# BMS-S02-V00-CellMonitor.net
KiCad netlist of a schematic drawn in Altium Designer
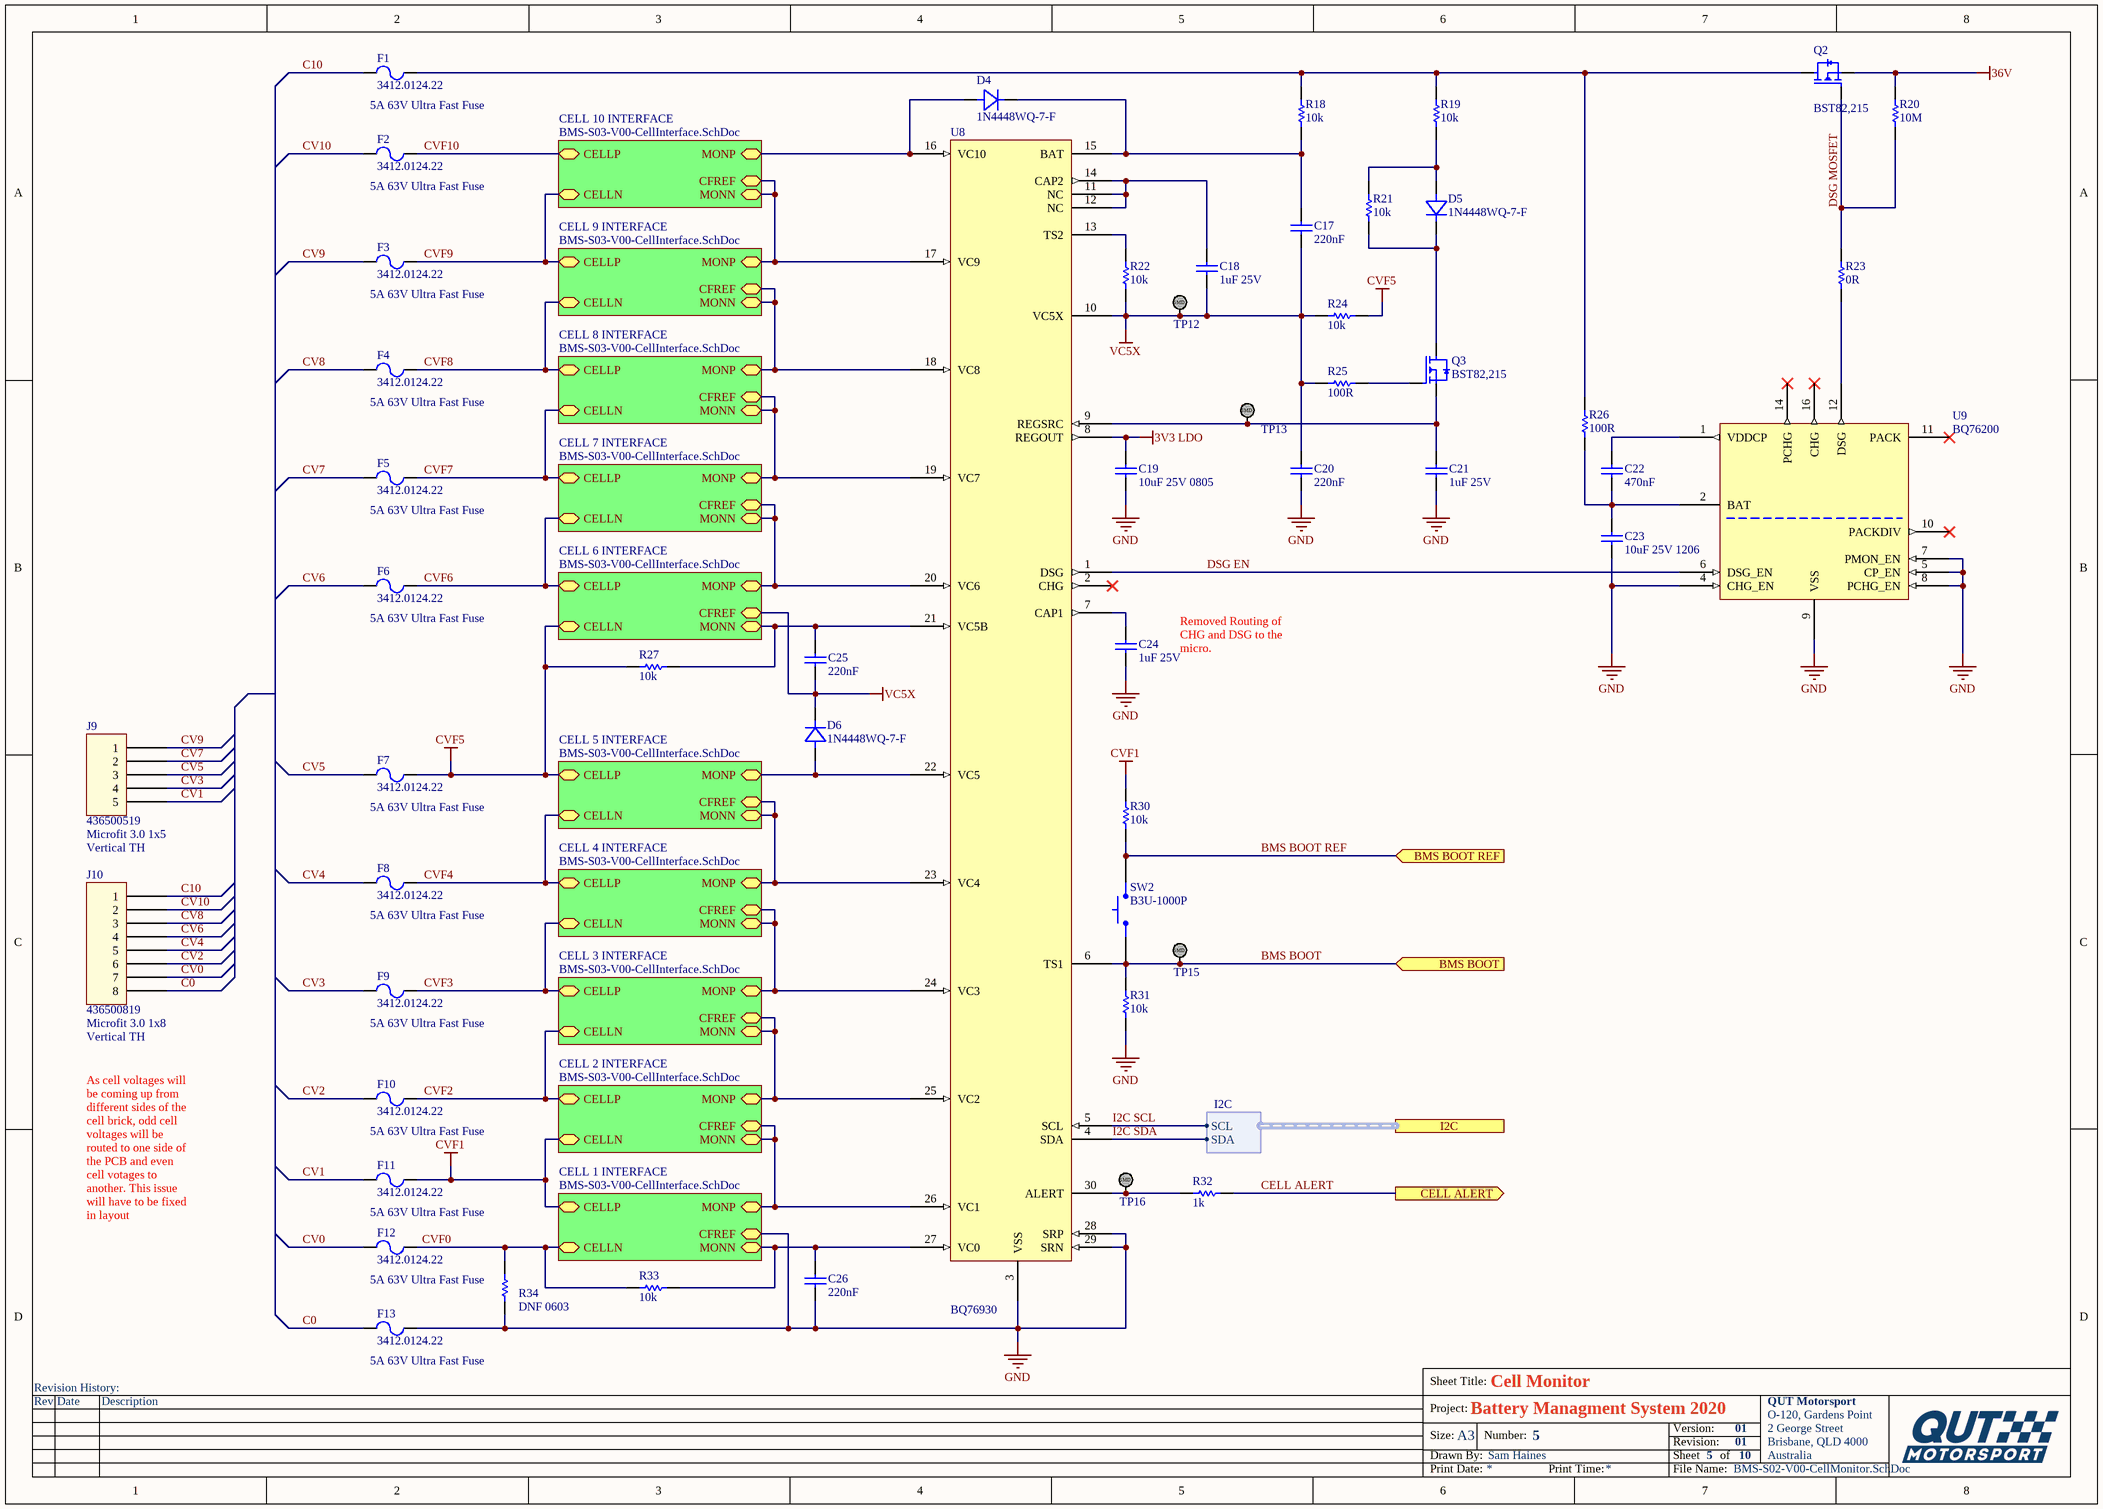
[diagram p0: BMS-S02-V00-CellMonitor.SchDoc]

(export (version "E")
  (design (tool "Eeschema 10.0.6"))
  (components
    (comp (ref "C17")
      (value "220nF")
      (footprint "Cap_Ceramic_0603")
      (description "Capacitor, Ceramic, SMD, 220nF, 50V, 5%, X7R, 0603")
      (libsource (lib "StandardCapacitors") (part "220nF 50V 5% X7R 0603"))
    )
    (comp (ref "C18")
      (value "1uF 25V")
      (footprint "Cap_Ceramic_0603")
      (description "Capacitor, Ceramic, SMD, 1uF, 25V, 5%, X7R, 0603")
      (libsource (lib "StandardCapacitors") (part "1uF 25V 5% X7R 0603"))
    )
    (comp (ref "C19")
      (value "10uF 25V 0805")
      (footprint "Cap_Ceramic_0805")
      (description "Capacitor, Ceramic, SMD, 10uF, 25V, 5%, X7R, 0805")
      (libsource (lib "StandardCapacitors") (part "10uF 25V 5% X7R 0805_1"))
    )
    (comp (ref "C20")
      (value "220nF")
      (footprint "Cap_Ceramic_0603")
      (description "Capacitor, Ceramic, SMD, 220nF, 50V, 5%, X7R, 0603")
      (libsource (lib "StandardCapacitors") (part "220nF 50V 5% X7R 0603"))
    )
    (comp (ref "C21")
      (value "1uF 25V")
      (footprint "Cap_Ceramic_0603")
      (description "Capacitor, Ceramic, SMD, 1uF, 25V, 5%, X7R, 0603")
      (libsource (lib "StandardCapacitors") (part "1uF 25V 5% X7R 0603"))
    )
    (comp (ref "C22")
      (value "470nF")
      (footprint "Cap_Ceramic_0603")
      (description "Capacitor, Ceramic, SMD, 470nF, 50V, 5%, X7R, 0603")
      (libsource (lib "StandardCapacitors") (part "470nF 50V 5% X7R 0603"))
    )
    (comp (ref "C23")
      (value "10uF 25V 1206")
      (footprint "Cap_Ceramic_1206")
      (description "Capacitor, Ceramic, SMD, 10uF, 25V, 10%, X7R, 1206")
      (libsource (lib "StandardCapacitors") (part "10uF 25V 10% X7R 1206"))
    )
    (comp (ref "C24")
      (value "1uF 25V")
      (footprint "Cap_Ceramic_0603")
      (description "Capacitor, Ceramic, SMD, 1uF, 25V, 5%, X7R, 0603")
      (libsource (lib "StandardCapacitors") (part "1uF 25V 5% X7R 0603"))
    )
    (comp (ref "C25")
      (value "220nF")
      (footprint "Cap_Ceramic_0603")
      (description "Capacitor, Ceramic, SMD, 220nF, 50V, 5%, X7R, 0603")
      (libsource (lib "StandardCapacitors") (part "220nF 50V 5% X7R 0603"))
    )
    (comp (ref "C26")
      (value "220nF")
      (footprint "Cap_Ceramic_0603")
      (description "Capacitor, Ceramic, SMD, 220nF, 50V, 5%, X7R, 0603")
      (libsource (lib "StandardCapacitors") (part "220nF 50V 5% X7R 0603"))
    )
    (comp (ref "D4")
      (value "1N4448WQ-7-F")
      (footprint "SMA")
      (description "Diode, SMD, 75V, 5%, 250mA, SOD123")
      (fields
        (field (name "MANUFACTURER") "ON Semiconductor / Fairchild")
        (field (name "MANUFACTURER PART NUMBER") "1N914BWS")
      )
      (libsource (lib "QUTMS_DiodeLibrary") (part "1N4448WQ-7-F"))
    )
    (comp (ref "D5")
      (value "1N4448WQ-7-F")
      (footprint "SMA")
      (description "Diode, SMD, 75V, 5%, 250mA, SOD123")
      (fields
        (field (name "MANUFACTURER") "ON Semiconductor / Fairchild")
        (field (name "MANUFACTURER PART NUMBER") "1N914BWS")
      )
      (libsource (lib "QUTMS_DiodeLibrary") (part "1N4448WQ-7-F"))
    )
    (comp (ref "D6")
      (value "1N4448WQ-7-F")
      (footprint "SMA")
      (description "Diode, SMD, 75V, 5%, 250mA, SOD123")
      (fields
        (field (name "MANUFACTURER") "ON Semiconductor / Fairchild")
        (field (name "MANUFACTURER PART NUMBER") "1N914BWS")
      )
      (libsource (lib "QUTMS_DiodeLibrary") (part "1N4448WQ-7-F"))
    )
    (comp (ref "F1")
      (value "3412.0124.22")
      (footprint "3412.0124.22")
      (description "FUSE BOARD MOUNT 5A 63VDC 0603")
      (libsource (lib "CellMonitor") (part "3412.0124.22"))
    )
    (comp (ref "F2")
      (value "3412.0124.22")
      (footprint "3412.0124.22")
      (description "FUSE BOARD MOUNT 5A 63VDC 0603")
      (libsource (lib "CellMonitor") (part "3412.0124.22"))
    )
    (comp (ref "F3")
      (value "3412.0124.22")
      (footprint "3412.0124.22")
      (description "FUSE BOARD MOUNT 5A 63VDC 0603")
      (libsource (lib "CellMonitor") (part "3412.0124.22"))
    )
    (comp (ref "F4")
      (value "3412.0124.22")
      (footprint "3412.0124.22")
      (description "FUSE BOARD MOUNT 5A 63VDC 0603")
      (libsource (lib "CellMonitor") (part "3412.0124.22"))
    )
    (comp (ref "F5")
      (value "3412.0124.22")
      (footprint "3412.0124.22")
      (description "FUSE BOARD MOUNT 5A 63VDC 0603")
      (libsource (lib "CellMonitor") (part "3412.0124.22"))
    )
    (comp (ref "F6")
      (value "3412.0124.22")
      (footprint "3412.0124.22")
      (description "FUSE BOARD MOUNT 5A 63VDC 0603")
      (libsource (lib "CellMonitor") (part "3412.0124.22"))
    )
    (comp (ref "F7")
      (value "3412.0124.22")
      (footprint "3412.0124.22")
      (description "FUSE BOARD MOUNT 5A 63VDC 0603")
      (libsource (lib "CellMonitor") (part "3412.0124.22"))
    )
    (comp (ref "F8")
      (value "3412.0124.22")
      (footprint "3412.0124.22")
      (description "FUSE BOARD MOUNT 5A 63VDC 0603")
      (libsource (lib "CellMonitor") (part "3412.0124.22"))
    )
    (comp (ref "F9")
      (value "3412.0124.22")
      (footprint "3412.0124.22")
      (description "FUSE BOARD MOUNT 5A 63VDC 0603")
      (libsource (lib "CellMonitor") (part "3412.0124.22"))
    )
    (comp (ref "F10")
      (value "3412.0124.22")
      (footprint "3412.0124.22")
      (description "FUSE BOARD MOUNT 5A 63VDC 0603")
      (libsource (lib "CellMonitor") (part "3412.0124.22"))
    )
    (comp (ref "F11")
      (value "3412.0124.22")
      (footprint "3412.0124.22")
      (description "FUSE BOARD MOUNT 5A 63VDC 0603")
      (libsource (lib "CellMonitor") (part "3412.0124.22"))
    )
    (comp (ref "F12")
      (value "3412.0124.22")
      (footprint "3412.0124.22")
      (description "FUSE BOARD MOUNT 5A 63VDC 0603")
      (libsource (lib "CellMonitor") (part "3412.0124.22"))
    )
    (comp (ref "F13")
      (value "3412.0124.22")
      (footprint "3412.0124.22")
      (description "FUSE BOARD MOUNT 5A 63VDC 0603")
      (libsource (lib "CellMonitor") (part "3412.0124.22"))
    )
    (comp (ref "J9")
      (value "436500519")
      (footprint "Microfit_1X5_V_TH")
      (libsource (lib "QUTMS_MicrofitLibrary") (part "Microfit_1x5"))
    )
    (comp (ref "J10")
      (value "436500819")
      (footprint "Microfit_1X8_V_TH")
      (libsource (lib "QUTMS_MicrofitLibrary") (part "Microfit_1x8"))
    )
    (comp (ref "Q2")
      (value "BST82,215")
      (footprint "BST82,215")
      (description "MOSFET N-CH, 20V, SOT23")
      (libsource (lib "") (part "BST82,215_1"))
    )
    (comp (ref "Q3")
      (value "BST82,215")
      (footprint "BST82,215")
      (description "MOSFET N-CH, 20V, SOT23")
      (libsource (lib "CellMonitor") (part "BST82,215"))
    )
    (comp (ref "R18")
      (value "10k")
      (footprint "Res_ThinFilm_0603")
      (description "Resistor, SMD, 10k, 0.1W, 5%, 0603")
      (libsource (lib "StandardResistors") (part "10k 5% 0603"))
    )
    (comp (ref "R19")
      (value "10k")
      (footprint "Res_ThinFilm_0603")
      (description "Resistor, SMD, 10k, 0.1W, 5%, 0603")
      (libsource (lib "StandardResistors") (part "10k 5% 0603"))
    )
    (comp (ref "R20")
      (value "10M")
      (footprint "Res_ThinFilm_0603")
      (description "Resistor, SMD, 10M, 0.1W, 5%, 0603")
      (libsource (lib "StandardResistors") (part "10M 5% 0603"))
    )
    (comp (ref "R21")
      (value "10k")
      (footprint "Res_ThinFilm_0603")
      (description "Resistor, SMD, 10k, 0.1W, 5%, 0603")
      (libsource (lib "StandardResistors") (part "10k 5% 0603"))
    )
    (comp (ref "R22")
      (value "10k")
      (footprint "Res_ThinFilm_0603")
      (description "Resistor, SMD, 10k, 0.1W, 5%, 0603")
      (libsource (lib "StandardResistors") (part "10k 5% 0603"))
    )
    (comp (ref "R23")
      (value "0R")
      (footprint "Res_ThinFilm_0603")
      (description "Resistor, SMD, 0R, 0.1W, 5%, 0603")
      (libsource (lib "StandardResistors") (part "0R 5% 0603"))
    )
    (comp (ref "R24")
      (value "10k")
      (footprint "Res_ThinFilm_0603")
      (description "Resistor, SMD, 10k, 0.1W, 5%, 0603")
      (libsource (lib "StandardResistors") (part "10k 5% 0603"))
    )
    (comp (ref "R25")
      (value "100R")
      (footprint "Res_ThinFilm_0603")
      (description "Resistor, SMD, 100R, 0.1W, 5%, 0603")
      (libsource (lib "StandardResistors") (part "100R 5%, 0603"))
    )
    (comp (ref "R26")
      (value "100R")
      (footprint "Res_ThinFilm_0603")
      (description "Resistor, SMD, 100R, 0.1W, 5%, 0603")
      (libsource (lib "StandardResistors") (part "100R 5%, 0603"))
    )
    (comp (ref "R27")
      (value "10k")
      (footprint "Res_ThinFilm_0603")
      (description "Resistor, SMD, 10k, 0.1W, 5%, 0603")
      (libsource (lib "StandardResistors") (part "10k 5% 0603"))
    )
    (comp (ref "R30")
      (value "10k")
      (footprint "Res_ThinFilm_0603")
      (description "Resistor, SMD, 10k, 0.1W, 5%, 0603")
      (libsource (lib "StandardResistors") (part "10k 5% 0603"))
    )
    (comp (ref "R31")
      (value "10k")
      (footprint "Res_ThinFilm_0603")
      (description "Resistor, SMD, 10k, 0.1W, 5%, 0603")
      (libsource (lib "StandardResistors") (part "10k 5% 0603"))
    )
    (comp (ref "R32")
      (value "1k")
      (footprint "Res_ThinFilm_0603")
      (description "Resistor, SMD, 1k, 0.1W, 5%, 0603")
      (libsource (lib "StandardResistors") (part "1k 5% 0603"))
    )
    (comp (ref "R33")
      (value "10k")
      (footprint "Res_ThinFilm_0603")
      (description "Resistor, SMD, 10k, 0.1W, 5%, 0603")
      (libsource (lib "StandardResistors") (part "10k 5% 0603"))
    )
    (comp (ref "R34")
      (value "DNF 0603")
      (footprint "Res_ThinFilm_0603")
      (description "Resistor, SMD, DNF, 0.1W, 0603")
      (libsource (lib "StandardResistors") (part "DNF 0603"))
    )
    (comp (ref "SW2")
      (value "B3U-1000P")
      (footprint "BTN B3U-1000P")
      (description "Omron B3U-1000P Ultra Miniture Switch")
      (libsource (lib "QUTMS_SwitchLibrary") (part "BTN B3U-1000P"))
    )
    (comp (ref "TP12")
      (value "TestPoint_SMD")
      (footprint "TestPointSMD")
      (libsource (lib "StandardTest") (part "TestPoint_SMD"))
    )
    (comp (ref "TP13")
      (value "TestPoint_SMD")
      (footprint "TestPointSMD")
      (libsource (lib "StandardTest") (part "TestPoint_SMD"))
    )
    (comp (ref "TP15")
      (value "TestPoint_SMD")
      (footprint "TestPointSMD")
      (libsource (lib "StandardTest") (part "TestPoint_SMD"))
    )
    (comp (ref "TP16")
      (value "TestPoint_SMD")
      (footprint "TestPointSMD")
      (libsource (lib "StandardTest") (part "TestPoint_SMD"))
    )
    (comp (ref "U8")
      (value "BQ76930")
      (footprint "bq76930")
      (description "Battery Monitoring/Fuel Gauge Li-Ion/Li-Polymer/LiFePO4 0V to 16V 30-Pin TSSOP T/R")
      (fields (field (name "INTERNALPART") "Test1234") (field (name "MANUFACTURER") "Texas Instruments"))
      (libsource (lib "CellMonitor") (part "BQ76930"))
    )
    (comp (ref "U9")
      (value "BQ76200")
      (footprint "BQ76200")
      (description "High-voltage battery pack front-end charge/discharge high-side NFET driver")
      (fields (field (name "MPN") "BQ76200PWR") (field (name "MANUFACTURER") "Texas Instruments"))
      (libsource (lib "CellMonitor") (part "BQ76200PWR"))
    )
  )
  (nets
    (net (code "2") (name "/BMS BOOT") (class "Default")
      (node (ref "R31") (pin "2") (pinfunction "2_2") (pintype "passive"))
      (node (ref "SW2") (pin "1") (pinfunction "1_1") (pintype "passive"))
      (node (ref "TP15") (pin "1") (pinfunction "1_1") (pintype "passive"))
      (node (ref "U8") (pin "6") (pinfunction "TS1_6") (pintype "passive"))
    )
    (net (code "3") (name "/BMS BOOT REF") (class "Default")
      (node (ref "R30") (pin "1") (pinfunction "1_1") (pintype "passive"))
      (node (ref "SW2") (pin "2") (pinfunction "2_2") (pintype "passive"))
    )
    (net (code "4") (name "/C0") (class "Default")
      (node (ref "F13") (pin "1") (pinfunction "1_1") (pintype "passive"))
      (node (ref "J10") (pin "8") (pinfunction "8_8") (pintype "passive"))
    )
    (net (code "5") (name "/C10") (class "Default")
      (node (ref "F1") (pin "1") (pinfunction "1_1") (pintype "passive"))
      (node (ref "J10") (pin "1") (pinfunction "1_1") (pintype "passive"))
    )
    (net (code "6") (name "/CELL ALERT") (class "Default")
      (node (ref "R32") (pin "2") (pinfunction "2_2") (pintype "passive"))
    )
    (net (code "7") (name "/CFREF") (class "Default")
      (node (ref "U8") (pin "26") (pinfunction "VC1_26") (pintype "input"))
    )
    (net (code "8") (name "/CFREF_1") (class "Default")
      (node (ref "U8") (pin "17") (pinfunction "VC9_17") (pintype "input"))
    )
    (net (code "9") (name "/CFREF_2") (class "Default")
      (node (ref "U8") (pin "18") (pinfunction "VC8_18") (pintype "input"))
    )
    (net (code "10") (name "/CFREF_3") (class "Default")
      (node (ref "U8") (pin "19") (pinfunction "VC7_19") (pintype "input"))
    )
    (net (code "11") (name "/CFREF_4") (class "Default")
      (node (ref "U8") (pin "20") (pinfunction "VC6_20") (pintype "input"))
    )
    (net (code "12") (name "/CFREF_5") (class "Default")
      (node (ref "U8") (pin "23") (pinfunction "VC4_23") (pintype "input"))
    )
    (net (code "13") (name "/CFREF_6") (class "Default")
      (node (ref "U8") (pin "24") (pinfunction "VC3_24") (pintype "input"))
    )
    (net (code "14") (name "/CFREF_7") (class "Default")
      (node (ref "U8") (pin "25") (pinfunction "VC2_25") (pintype "input"))
    )
    (net (code "15") (name "/CV0") (class "Default")
      (node (ref "F12") (pin "1") (pinfunction "1_1") (pintype "passive"))
      (node (ref "J10") (pin "7") (pinfunction "7_7") (pintype "passive"))
    )
    (net (code "16") (name "/CV1") (class "Default")
      (node (ref "F11") (pin "1") (pinfunction "1_1") (pintype "passive"))
      (node (ref "J9") (pin "5") (pinfunction "5_5") (pintype "passive"))
    )
    (net (code "17") (name "/CV2") (class "Default")
      (node (ref "F10") (pin "1") (pinfunction "1_1") (pintype "passive"))
      (node (ref "J10") (pin "6") (pinfunction "6_6") (pintype "passive"))
    )
    (net (code "18") (name "/CV3") (class "Default")
      (node (ref "F9") (pin "1") (pinfunction "1_1") (pintype "passive"))
      (node (ref "J9") (pin "4") (pinfunction "4_4") (pintype "passive"))
    )
    (net (code "19") (name "/CV4") (class "Default")
      (node (ref "F8") (pin "1") (pinfunction "1_1") (pintype "passive"))
      (node (ref "J10") (pin "5") (pinfunction "5_5") (pintype "passive"))
    )
    (net (code "20") (name "/CV5") (class "Default")
      (node (ref "F7") (pin "1") (pinfunction "1_1") (pintype "passive"))
      (node (ref "J9") (pin "3") (pinfunction "3_3") (pintype "passive"))
    )
    (net (code "21") (name "/CV6") (class "Default")
      (node (ref "F6") (pin "1") (pinfunction "1_1") (pintype "passive"))
      (node (ref "J10") (pin "4") (pinfunction "4_4") (pintype "passive"))
    )
    (net (code "22") (name "/CV7") (class "Default")
      (node (ref "F5") (pin "1") (pinfunction "1_1") (pintype "passive"))
      (node (ref "J9") (pin "2") (pinfunction "2_2") (pintype "passive"))
    )
    (net (code "23") (name "/CV8") (class "Default")
      (node (ref "F4") (pin "1") (pinfunction "1_1") (pintype "passive"))
      (node (ref "J10") (pin "3") (pinfunction "3_3") (pintype "passive"))
    )
    (net (code "24") (name "/CV9") (class "Default")
      (node (ref "F3") (pin "1") (pinfunction "1_1") (pintype "passive"))
      (node (ref "J9") (pin "1") (pinfunction "1_1") (pintype "passive"))
    )
    (net (code "25") (name "/CV10") (class "Default")
      (node (ref "F2") (pin "1") (pinfunction "1_1") (pintype "passive"))
      (node (ref "J10") (pin "2") (pinfunction "2_2") (pintype "passive"))
    )
    (net (code "26") (name "/CVF0") (class "Default")
      (node (ref "F12") (pin "2") (pinfunction "2_2") (pintype "passive"))
      (node (ref "R33") (pin "1") (pinfunction "1_1") (pintype "passive"))
      (node (ref "R34") (pin "2") (pinfunction "2_2") (pintype "passive"))
    )
    (net (code "27") (name "/CVF2") (class "Default")
      (node (ref "F10") (pin "2") (pinfunction "2_2") (pintype "passive"))
    )
    (net (code "28") (name "/CVF3") (class "Default")
      (node (ref "F9") (pin "2") (pinfunction "2_2") (pintype "passive"))
    )
    (net (code "29") (name "/CVF4") (class "Default")
      (node (ref "F8") (pin "2") (pinfunction "2_2") (pintype "passive"))
    )
    (net (code "30") (name "/CVF6") (class "Default")
      (node (ref "F6") (pin "2") (pinfunction "2_2") (pintype "passive"))
    )
    (net (code "31") (name "/CVF7") (class "Default")
      (node (ref "F5") (pin "2") (pinfunction "2_2") (pintype "passive"))
    )
    (net (code "32") (name "/CVF8") (class "Default")
      (node (ref "F4") (pin "2") (pinfunction "2_2") (pintype "passive"))
    )
    (net (code "33") (name "/CVF9") (class "Default")
      (node (ref "F3") (pin "2") (pinfunction "2_2") (pintype "passive"))
    )
    (net (code "34") (name "/CVF10") (class "Default")
      (node (ref "F2") (pin "2") (pinfunction "2_2") (pintype "passive"))
    )
    (net (code "35") (name "/DSG EN") (class "Default")
      (node (ref "U8") (pin "1") (pinfunction "DSG_1") (pintype "output"))
      (node (ref "U9") (pin "6") (pinfunction "DSG_EN_6") (pintype "input"))
    )
    (net (code "36") (name "/DSG MOSFET") (class "Default")
      (node (ref "Q2") (pin "G") (pinfunction "Gate_G") (pintype "passive"))
      (node (ref "R20") (pin "1") (pinfunction "1_1") (pintype "passive"))
      (node (ref "R23") (pin "2") (pinfunction "2_2") (pintype "passive"))
    )
    (net (code "37") (name "/I2C SCL") (class "Default")
      (node (ref "U8") (pin "5") (pinfunction "SCL_5") (pintype "input"))
    )
    (net (code "38") (name "/I2C SDA") (class "Default")
      (node (ref "U8") (pin "4") (pinfunction "SDA_4") (pintype "passive"))
    )
    (net (code "39") (name "/MONN") (class "Default")
      (node (ref "C26") (pin "2") (pinfunction "2_2") (pintype "passive"))
      (node (ref "R33") (pin "2") (pinfunction "2_2") (pintype "passive"))
      (node (ref "U8") (pin "27") (pinfunction "VC0_27") (pintype "input"))
    )
    (net (code "40") (name "/MONN_1") (class "Default")
      (node (ref "C25") (pin "2") (pinfunction "2_2") (pintype "passive"))
      (node (ref "R27") (pin "2") (pinfunction "2_2") (pintype "passive"))
      (node (ref "U8") (pin "21") (pinfunction "VC5B_21") (pintype "input"))
    )
    (net (code "41") (name "/MONP") (class "Default")
      (node (ref "D6") (pin "A") (pinfunction "Anode_A") (pintype "passive"))
      (node (ref "U8") (pin "22") (pinfunction "VC5_22") (pintype "input"))
    )
    (net (code "42") (name "/MONP_1") (class "Default")
      (node (ref "D4") (pin "A") (pinfunction "Anode_A") (pintype "passive"))
      (node (ref "U8") (pin "16") (pinfunction "VC10_16") (pintype "input"))
    )
    (net (code "44") (name "3V3 LDO") (class "Default")
      (node (ref "C19") (pin "2") (pinfunction "2_2") (pintype "passive"))
      (node (ref "U8") (pin "8") (pinfunction "REGOUT_8") (pintype "output"))
    )
    (net (code "45") (name "36V") (class "Default")
      (node (ref "Q2") (pin "S") (pinfunction "Source_S") (pintype "passive"))
      (node (ref "R20") (pin "2") (pinfunction "2_2") (pintype "passive"))
    )
    (net (code "46") (name "CVF1") (class "Default")
      (node (ref "F11") (pin "2") (pinfunction "2_2") (pintype "passive"))
      (node (ref "R30") (pin "2") (pinfunction "2_2") (pintype "passive"))
    )
    (net (code "47") (name "CVF5") (class "Default")
      (node (ref "F7") (pin "2") (pinfunction "2_2") (pintype "passive"))
      (node (ref "R24") (pin "2") (pinfunction "2_2") (pintype "passive"))
      (node (ref "R27") (pin "1") (pinfunction "1_1") (pintype "passive"))
    )
    (net (code "48") (name "GND") (class "Default")
      (node (ref "C19") (pin "1") (pinfunction "1_1") (pintype "passive"))
      (node (ref "C20") (pin "1") (pinfunction "1_1") (pintype "passive"))
      (node (ref "C21") (pin "1") (pinfunction "1_1") (pintype "passive"))
      (node (ref "C23") (pin "1") (pinfunction "1_1") (pintype "passive"))
      (node (ref "C24") (pin "1") (pinfunction "1_1") (pintype "passive"))
      (node (ref "C26") (pin "1") (pinfunction "1_1") (pintype "passive"))
      (node (ref "F13") (pin "2") (pinfunction "2_2") (pintype "passive"))
      (node (ref "R31") (pin "1") (pinfunction "1_1") (pintype "passive"))
      (node (ref "R34") (pin "1") (pinfunction "1_1") (pintype "passive"))
      (node (ref "U8") (pin "28") (pinfunction "SRP_28") (pintype "input"))
      (node (ref "U8") (pin "29") (pinfunction "SRN_29") (pintype "input"))
      (node (ref "U8") (pin "3") (pinfunction "VSS_3") (pintype "power_in"))
      (node (ref "U9") (pin "4") (pinfunction "CHG_EN_4") (pintype "input"))
      (node (ref "U9") (pin "5") (pinfunction "CP_EN_5") (pintype "input"))
      (node (ref "U9") (pin "7") (pinfunction "PMON_EN_7") (pintype "input"))
      (node (ref "U9") (pin "8") (pinfunction "PCHG_EN_8") (pintype "input"))
      (node (ref "U9") (pin "9") (pinfunction "VSS_9") (pintype "passive"))
    )
    (net (code "49") (name "Net-(D4-Cathode)") (class "Default")
      (node (ref "C17") (pin "2") (pinfunction "2_2") (pintype "passive"))
      (node (ref "D4") (pin "K") (pinfunction "Cathode_K") (pintype "passive"))
      (node (ref "R18") (pin "1") (pinfunction "1_1") (pintype "passive"))
      (node (ref "U8") (pin "15") (pinfunction "BAT_15") (pintype "power_in"))
    )
    (net (code "50") (name "Net-(D5-Anode)") (class "Default")
      (node (ref "D5") (pin "A") (pinfunction "Anode_A") (pintype "passive"))
      (node (ref "R19") (pin "1") (pinfunction "1_1") (pintype "passive"))
      (node (ref "R21") (pin "2") (pinfunction "2_2") (pintype "passive"))
    )
    (net (code "51") (name "Net-(D5-Cathode)") (class "Default")
      (node (ref "D5") (pin "K") (pinfunction "Cathode_K") (pintype "passive"))
      (node (ref "Q3") (pin "D") (pinfunction "Drain_D") (pintype "passive"))
      (node (ref "R21") (pin "1") (pinfunction "1_1") (pintype "passive"))
    )
    (net (code "52") (name "Net-(Q2-Drain)") (class "Default")
      (node (ref "F1") (pin "2") (pinfunction "2_2") (pintype "passive"))
      (node (ref "Q2") (pin "D") (pinfunction "Drain_D") (pintype "passive"))
      (node (ref "R18") (pin "2") (pinfunction "2_2") (pintype "passive"))
      (node (ref "R19") (pin "2") (pinfunction "2_2") (pintype "passive"))
      (node (ref "R26") (pin "2") (pinfunction "2_2") (pintype "passive"))
    )
    (net (code "53") (name "Net-(Q3-Gate)") (class "Default")
      (node (ref "Q3") (pin "G") (pinfunction "Gate_G") (pintype "passive"))
      (node (ref "R25") (pin "1") (pinfunction "1_1") (pintype "passive"))
    )
    (net (code "54") (name "Net-(Q3-Source)") (class "Default")
      (node (ref "C21") (pin "2") (pinfunction "2_2") (pintype "passive"))
      (node (ref "Q3") (pin "S") (pinfunction "Source_S") (pintype "passive"))
      (node (ref "TP13") (pin "1") (pinfunction "1_1") (pintype "passive"))
      (node (ref "U8") (pin "9") (pinfunction "REGSRC_9") (pintype "input"))
    )
    (net (code "55") (name "Net-(U8-ALERT)") (class "Default")
      (node (ref "R32") (pin "1") (pinfunction "1_1") (pintype "passive"))
      (node (ref "TP16") (pin "1") (pinfunction "1_1") (pintype "passive"))
      (node (ref "U8") (pin "30") (pinfunction "ALERT_30") (pintype "passive"))
    )
    (net (code "56") (name "Net-(U8-CAP1)") (class "Default")
      (node (ref "C24") (pin "2") (pinfunction "2_2") (pintype "passive"))
      (node (ref "U8") (pin "7") (pinfunction "CAP1_7") (pintype "output"))
    )
    (net (code "57") (name "Net-(U8-CAP2)") (class "Default")
      (node (ref "C18") (pin "2") (pinfunction "2_2") (pintype "passive"))
      (node (ref "U8") (pin "11") (pinfunction "NC_11") (pintype "power_in"))
      (node (ref "U8") (pin "12") (pinfunction "NC_12") (pintype "power_in"))
      (node (ref "U8") (pin "14") (pinfunction "CAP2_14") (pintype "output"))
    )
    (net (code "58") (name "Net-(U8-TS2)") (class "Default")
      (node (ref "R22") (pin "2") (pinfunction "2_2") (pintype "passive"))
      (node (ref "U8") (pin "13") (pinfunction "TS2_13") (pintype "passive"))
    )
    (net (code "59") (name "Net-(U9-BAT)") (class "Default")
      (node (ref "C22") (pin "1") (pinfunction "1_1") (pintype "passive"))
      (node (ref "C23") (pin "2") (pinfunction "2_2") (pintype "passive"))
      (node (ref "R26") (pin "1") (pinfunction "1_1") (pintype "passive"))
      (node (ref "U9") (pin "2") (pinfunction "BAT_2") (pintype "passive"))
    )
    (net (code "60") (name "Net-(U9-DSG)") (class "Default")
      (node (ref "R23") (pin "1") (pinfunction "1_1") (pintype "passive"))
      (node (ref "U9") (pin "12") (pinfunction "DSG_12") (pintype "output"))
    )
    (net (code "61") (name "Net-(U9-VDDCP)") (class "Default")
      (node (ref "C22") (pin "2") (pinfunction "2_2") (pintype "passive"))
      (node (ref "U9") (pin "1") (pinfunction "VDDCP_1") (pintype "output"))
    )
    (net (code "62") (name "VC5X") (class "Default")
      (node (ref "C17") (pin "1") (pinfunction "1_1") (pintype "passive"))
      (node (ref "C18") (pin "1") (pinfunction "1_1") (pintype "passive"))
      (node (ref "C20") (pin "2") (pinfunction "2_2") (pintype "passive"))
      (node (ref "C25") (pin "1") (pinfunction "1_1") (pintype "passive"))
      (node (ref "D6") (pin "K") (pinfunction "Cathode_K") (pintype "passive"))
      (node (ref "R22") (pin "1") (pinfunction "1_1") (pintype "passive"))
      (node (ref "R24") (pin "1") (pinfunction "1_1") (pintype "passive"))
      (node (ref "R25") (pin "2") (pinfunction "2_2") (pintype "passive"))
      (node (ref "TP12") (pin "1") (pinfunction "1_1") (pintype "passive"))
      (node (ref "U8") (pin "10") (pinfunction "VC5X_10") (pintype "power_in"))
    )
    (net (code "63") (name "unconnected-(U8-CHG-Pad2)") (class "Default")
      (node (ref "U8") (pin "2") (pinfunction "CHG_2") (pintype "output+no_connect"))
    )
    (net (code "64") (name "unconnected-(U9-CHG-Pad16)") (class "Default")
      (node (ref "U9") (pin "16") (pinfunction "CHG_16") (pintype "output+no_connect"))
    )
    (net (code "65") (name "unconnected-(U9-PACK-Pad11)") (class "Default")
      (node (ref "U9") (pin "11") (pinfunction "PACK_11") (pintype "passive+no_connect"))
    )
    (net (code "66") (name "unconnected-(U9-PACKDIV-Pad10)") (class "Default")
      (node (ref "U9") (pin "10") (pinfunction "PACKDIV_10") (pintype "output+no_connect"))
    )
    (net (code "67") (name "unconnected-(U9-PCHG-Pad14)") (class "Default")
      (node (ref "U9") (pin "14") (pinfunction "PCHG_14") (pintype "output+no_connect"))
    )
  )
)
